# 01_Power.net
KiCad netlist of a schematic drawn in Altium Designer
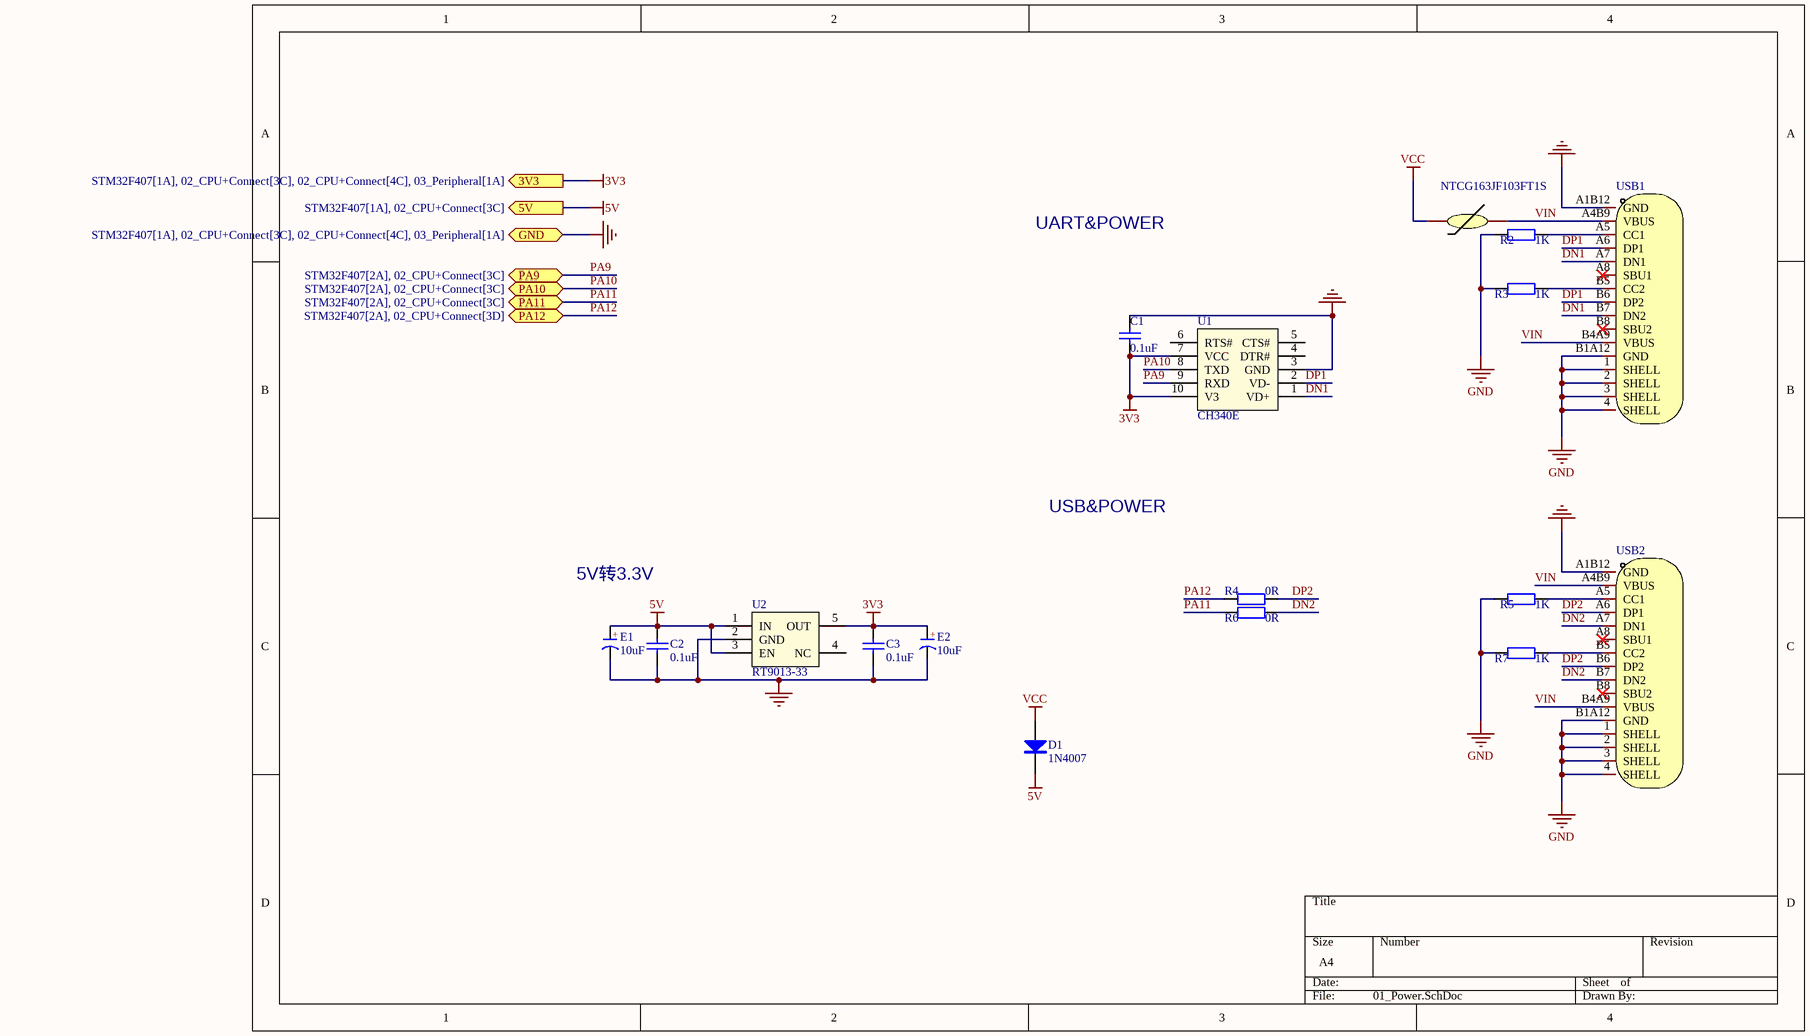
[diagram p0: 01_Power.SchDoc]

(export (version "E")
  (design (tool "Eeschema 10.0.6"))
  (components
    (comp (ref "C1") (value "0.1uF") (footprint "C 0402_L") (libsource (lib "Schlib1") (part "Cap")))
    (comp (ref "C2") (value "0.1uF") (footprint "C 0402_L") (libsource (lib "Schlib1") (part "Cap")))
    (comp (ref "C3") (value "0.1uF") (footprint "C 0402_L") (libsource (lib "Schlib1") (part "Cap")))
    (comp (ref "D1")
      (value "1N4007")
      (footprint "SOD-123")
      (description "整流二极管")
      (libsource (lib "Schlib1") (part "1N4007"))
    )
    (comp (ref "E1")
      (value "10uF")
      (footprint "CD A(3216)")
      (description "贴片钽电容")
      (libsource (lib "Schlib1") (part "C-CD"))
    )
    (comp (ref "E2")
      (value "10uF")
      (footprint "CD A(3216)")
      (description "贴片钽电容")
      (libsource (lib "Schlib1") (part "C-CD"))
    )
    (comp (ref "R1")
      (value "NTCG163JF103FT1S")
      (footprint "R0603")
      (fields
        (field (name "MANUFACTURER") "TDK")
        (field (name "POWER") "100mW")
        (field (name "NAME") "NTCG163JF103FT1S")
      )
      (libsource (lib "YHT_Y170_SCH") (part "NTCG163JF103FT1S"))
    )
    (comp (ref "R2") (value "1K") (footprint "R 0402_L") (libsource (lib "Schlib1") (part "Res")))
    (comp (ref "R3") (value "1K") (footprint "R 0402_L") (libsource (lib "Schlib1") (part "Res")))
    (comp (ref "R4") (value "0R") (footprint "R 0402_L") (libsource (lib "") (part "Res_1")))
    (comp (ref "R5") (value "1K") (footprint "R 0402_L") (libsource (lib "Schlib1") (part "Res")))
    (comp (ref "R6") (value "0R") (footprint "R 0402_L") (libsource (lib "") (part "Res_1")))
    (comp (ref "R7") (value "1K") (footprint "R 0402_L") (libsource (lib "Schlib1") (part "Res")))
    (comp (ref "U1") (value "CH340E") (footprint "MSOP10_L") (libsource (lib "Schlib1") (part "CH340E")))
    (comp (ref "U2")
      (value "RT9013-33")
      (footprint "SOT23-5N")
      (libsource (lib "Schlib1") (part "RT9013-33"))
    )
    (comp (ref "USB1")
      (value "TYPE-C 16P(073)")
      (footprint "USB-C-SMD_TYPE-C16PIN_C668624")
      (description "连接器类型:Type-C;标准:-;公母:母座;触点数量:16;端口数量:1;安装方式:卧贴;额定电流 - 电源:5A;工作温度范围:-25℃~+85℃;")
      (fields (field (name "MANUFACTURER") "SHOU HAN(首韩)"))
      (libsource (lib "YHT_Y170_SCH") (part "TYPE-C 16P(073)"))
    )
    (comp (ref "USB2")
      (value "TYPE-C 16P(073)")
      (footprint "USB-C-SMD_TYPE-C16PIN_C668624")
      (description "连接器类型:Type-C;标准:-;公母:母座;触点数量:16;端口数量:1;安装方式:卧贴;额定电流 - 电源:5A;工作温度范围:-25℃~+85℃;")
      (fields (field (name "MANUFACTURER") "SHOU HAN(首韩)"))
      (libsource (lib "YHT_Y170_SCH") (part "TYPE-C 16P(073)"))
    )
  )
  (nets
    (net (code "1") (name "/DN1") (class "Default")
      (node (ref "U1") (pin "1") (pinfunction "VD+_1") (pintype "passive"))
      (node (ref "USB1") (pin "A7") (pinfunction "DN1_A7") (pintype "passive"))
      (node (ref "USB1") (pin "B7") (pinfunction "DN2_B7") (pintype "passive"))
    )
    (net (code "2") (name "/DN2") (class "Default")
      (node (ref "R6") (pin "1") (pinfunction "1_1") (pintype "passive"))
      (node (ref "USB2") (pin "A7") (pinfunction "DN1_A7") (pintype "passive"))
      (node (ref "USB2") (pin "B7") (pinfunction "DN2_B7") (pintype "passive"))
    )
    (net (code "3") (name "/DP1") (class "Default")
      (node (ref "U1") (pin "2") (pinfunction "VD-_2") (pintype "passive"))
      (node (ref "USB1") (pin "A6") (pinfunction "DP1_A6") (pintype "passive"))
      (node (ref "USB1") (pin "B6") (pinfunction "DP2_B6") (pintype "passive"))
    )
    (net (code "4") (name "/DP2") (class "Default")
      (node (ref "R4") (pin "1") (pinfunction "1_1") (pintype "passive"))
      (node (ref "USB2") (pin "A6") (pinfunction "DP1_A6") (pintype "passive"))
      (node (ref "USB2") (pin "B6") (pinfunction "DP2_B6") (pintype "passive"))
    )
    (net (code "5") (name "/PA9") (class "Default")
      (node (ref "U1") (pin "9") (pinfunction "RXD_9") (pintype "passive"))
    )
    (net (code "6") (name "/PA10") (class "Default")
      (node (ref "U1") (pin "8") (pinfunction "TXD_8") (pintype "passive"))
    )
    (net (code "7") (name "/PA11") (class "Default")
      (node (ref "R6") (pin "2") (pinfunction "2_2") (pintype "passive"))
    )
    (net (code "8") (name "/PA12") (class "Default")
      (node (ref "R4") (pin "2") (pinfunction "2_2") (pintype "passive"))
    )
    (net (code "9") (name "/VIN") (class "Default")
      (node (ref "R1") (pin "2") (pinfunction "2_2") (pintype "passive"))
      (node (ref "USB1") (pin "A4B9") (pinfunction "VBUS_A4B9") (pintype "passive"))
      (node (ref "USB1") (pin "B4A9") (pinfunction "VBUS_B4A9") (pintype "passive"))
      (node (ref "USB2") (pin "A4B9") (pinfunction "VBUS_A4B9") (pintype "passive"))
      (node (ref "USB2") (pin "B4A9") (pinfunction "VBUS_B4A9") (pintype "passive"))
    )
    (net (code "10") (name "3V3") (class "Default")
      (node (ref "C1") (pin "2") (pinfunction "2_2") (pintype "passive"))
      (node (ref "C3") (pin "2") (pinfunction "2_2") (pintype "passive"))
      (node (ref "E2") (pin "1") (pinfunction "A_1") (pintype "passive"))
      (node (ref "U1") (pin "10") (pinfunction "V3_10") (pintype "passive"))
      (node (ref "U1") (pin "7") (pinfunction "VCC_7") (pintype "passive"))
      (node (ref "U2") (pin "5") (pinfunction "OUT_5") (pintype "passive"))
    )
    (net (code "11") (name "5V") (class "Default")
      (node (ref "C2") (pin "2") (pinfunction "2_2") (pintype "passive"))
      (node (ref "D1") (pin "2") (pinfunction "K_2") (pintype "passive"))
      (node (ref "E1") (pin "1") (pinfunction "A_1") (pintype "passive"))
      (node (ref "U2") (pin "1") (pinfunction "IN_1") (pintype "passive"))
      (node (ref "U2") (pin "3") (pinfunction "EN_3") (pintype "passive"))
    )
    (net (code "12") (name "GND") (class "Default")
      (node (ref "C1") (pin "1") (pinfunction "1_1") (pintype "passive"))
      (node (ref "C2") (pin "1") (pinfunction "1_1") (pintype "passive"))
      (node (ref "C3") (pin "1") (pinfunction "1_1") (pintype "passive"))
      (node (ref "E1") (pin "2") (pinfunction "K_2") (pintype "passive"))
      (node (ref "E2") (pin "2") (pinfunction "K_2") (pintype "passive"))
      (node (ref "R2") (pin "1") (pinfunction "1_1") (pintype "passive"))
      (node (ref "R3") (pin "1") (pinfunction "1_1") (pintype "passive"))
      (node (ref "R5") (pin "1") (pinfunction "1_1") (pintype "passive"))
      (node (ref "R7") (pin "1") (pinfunction "1_1") (pintype "passive"))
      (node (ref "U1") (pin "3") (pinfunction "GND_3") (pintype "passive"))
      (node (ref "U2") (pin "2") (pinfunction "GND_2") (pintype "passive"))
      (node (ref "USB1") (pin "1") (pinfunction "SHELL_1") (pintype "passive"))
      (node (ref "USB1") (pin "2") (pinfunction "SHELL_2") (pintype "passive"))
      (node (ref "USB1") (pin "3") (pinfunction "SHELL_3") (pintype "passive"))
      (node (ref "USB1") (pin "4") (pinfunction "SHELL_4") (pintype "passive"))
      (node (ref "USB1") (pin "A1B12") (pinfunction "GND_A1B12") (pintype "passive"))
      (node (ref "USB1") (pin "B1A12") (pinfunction "GND_B1A12") (pintype "passive"))
      (node (ref "USB2") (pin "1") (pinfunction "SHELL_1") (pintype "passive"))
      (node (ref "USB2") (pin "2") (pinfunction "SHELL_2") (pintype "passive"))
      (node (ref "USB2") (pin "3") (pinfunction "SHELL_3") (pintype "passive"))
      (node (ref "USB2") (pin "4") (pinfunction "SHELL_4") (pintype "passive"))
      (node (ref "USB2") (pin "A1B12") (pinfunction "GND_A1B12") (pintype "passive"))
      (node (ref "USB2") (pin "B1A12") (pinfunction "GND_B1A12") (pintype "passive"))
    )
    (net (code "13") (name "Net-(USB1-CC1)") (class "Default")
      (node (ref "R2") (pin "2") (pinfunction "2_2") (pintype "passive"))
      (node (ref "USB1") (pin "A5") (pinfunction "CC1_A5") (pintype "passive"))
    )
    (net (code "14") (name "Net-(USB1-CC2)") (class "Default")
      (node (ref "R3") (pin "2") (pinfunction "2_2") (pintype "passive"))
      (node (ref "USB1") (pin "B5") (pinfunction "CC2_B5") (pintype "passive"))
    )
    (net (code "15") (name "Net-(USB2-CC1)") (class "Default")
      (node (ref "R5") (pin "2") (pinfunction "2_2") (pintype "passive"))
      (node (ref "USB2") (pin "A5") (pinfunction "CC1_A5") (pintype "passive"))
    )
    (net (code "16") (name "Net-(USB2-CC2)") (class "Default")
      (node (ref "R7") (pin "2") (pinfunction "2_2") (pintype "passive"))
      (node (ref "USB2") (pin "B5") (pinfunction "CC2_B5") (pintype "passive"))
    )
    (net (code "17") (name "VCC") (class "Default")
      (node (ref "D1") (pin "1") (pinfunction "A_1") (pintype "passive"))
      (node (ref "R1") (pin "1") (pinfunction "1_1") (pintype "passive"))
    )
    (net (code "18") (name "unconnected-(U1-CTS#-Pad5)") (class "Default")
      (node (ref "U1") (pin "5") (pinfunction "CTS#_5") (pintype "passive"))
    )
    (net (code "19") (name "unconnected-(U1-DTR#-Pad4)") (class "Default")
      (node (ref "U1") (pin "4") (pinfunction "DTR#_4") (pintype "passive"))
    )
    (net (code "20") (name "unconnected-(U1-RTS#-Pad6)") (class "Default")
      (node (ref "U1") (pin "6") (pinfunction "RTS#_6") (pintype "passive"))
    )
    (net (code "21") (name "unconnected-(U2-NC-Pad4)") (class "Default")
      (node (ref "U2") (pin "4") (pinfunction "NC_4") (pintype "passive"))
    )
    (net (code "22") (name "unconnected-(USB1-SBU1-PadA8)") (class "Default")
      (node (ref "USB1") (pin "A8") (pinfunction "SBU1_A8") (pintype "passive+no_connect"))
    )
    (net (code "23") (name "unconnected-(USB1-SBU2-PadB8)") (class "Default")
      (node (ref "USB1") (pin "B8") (pinfunction "SBU2_B8") (pintype "passive+no_connect"))
    )
    (net (code "24") (name "unconnected-(USB2-SBU1-PadA8)") (class "Default")
      (node (ref "USB2") (pin "A8") (pinfunction "SBU1_A8") (pintype "passive+no_connect"))
    )
    (net (code "25") (name "unconnected-(USB2-SBU2-PadB8)") (class "Default")
      (node (ref "USB2") (pin "B8") (pinfunction "SBU2_B8") (pintype "passive+no_connect"))
    )
  )
)
